# main.net
KiCad netlist of a schematic drawn in Altium Designer
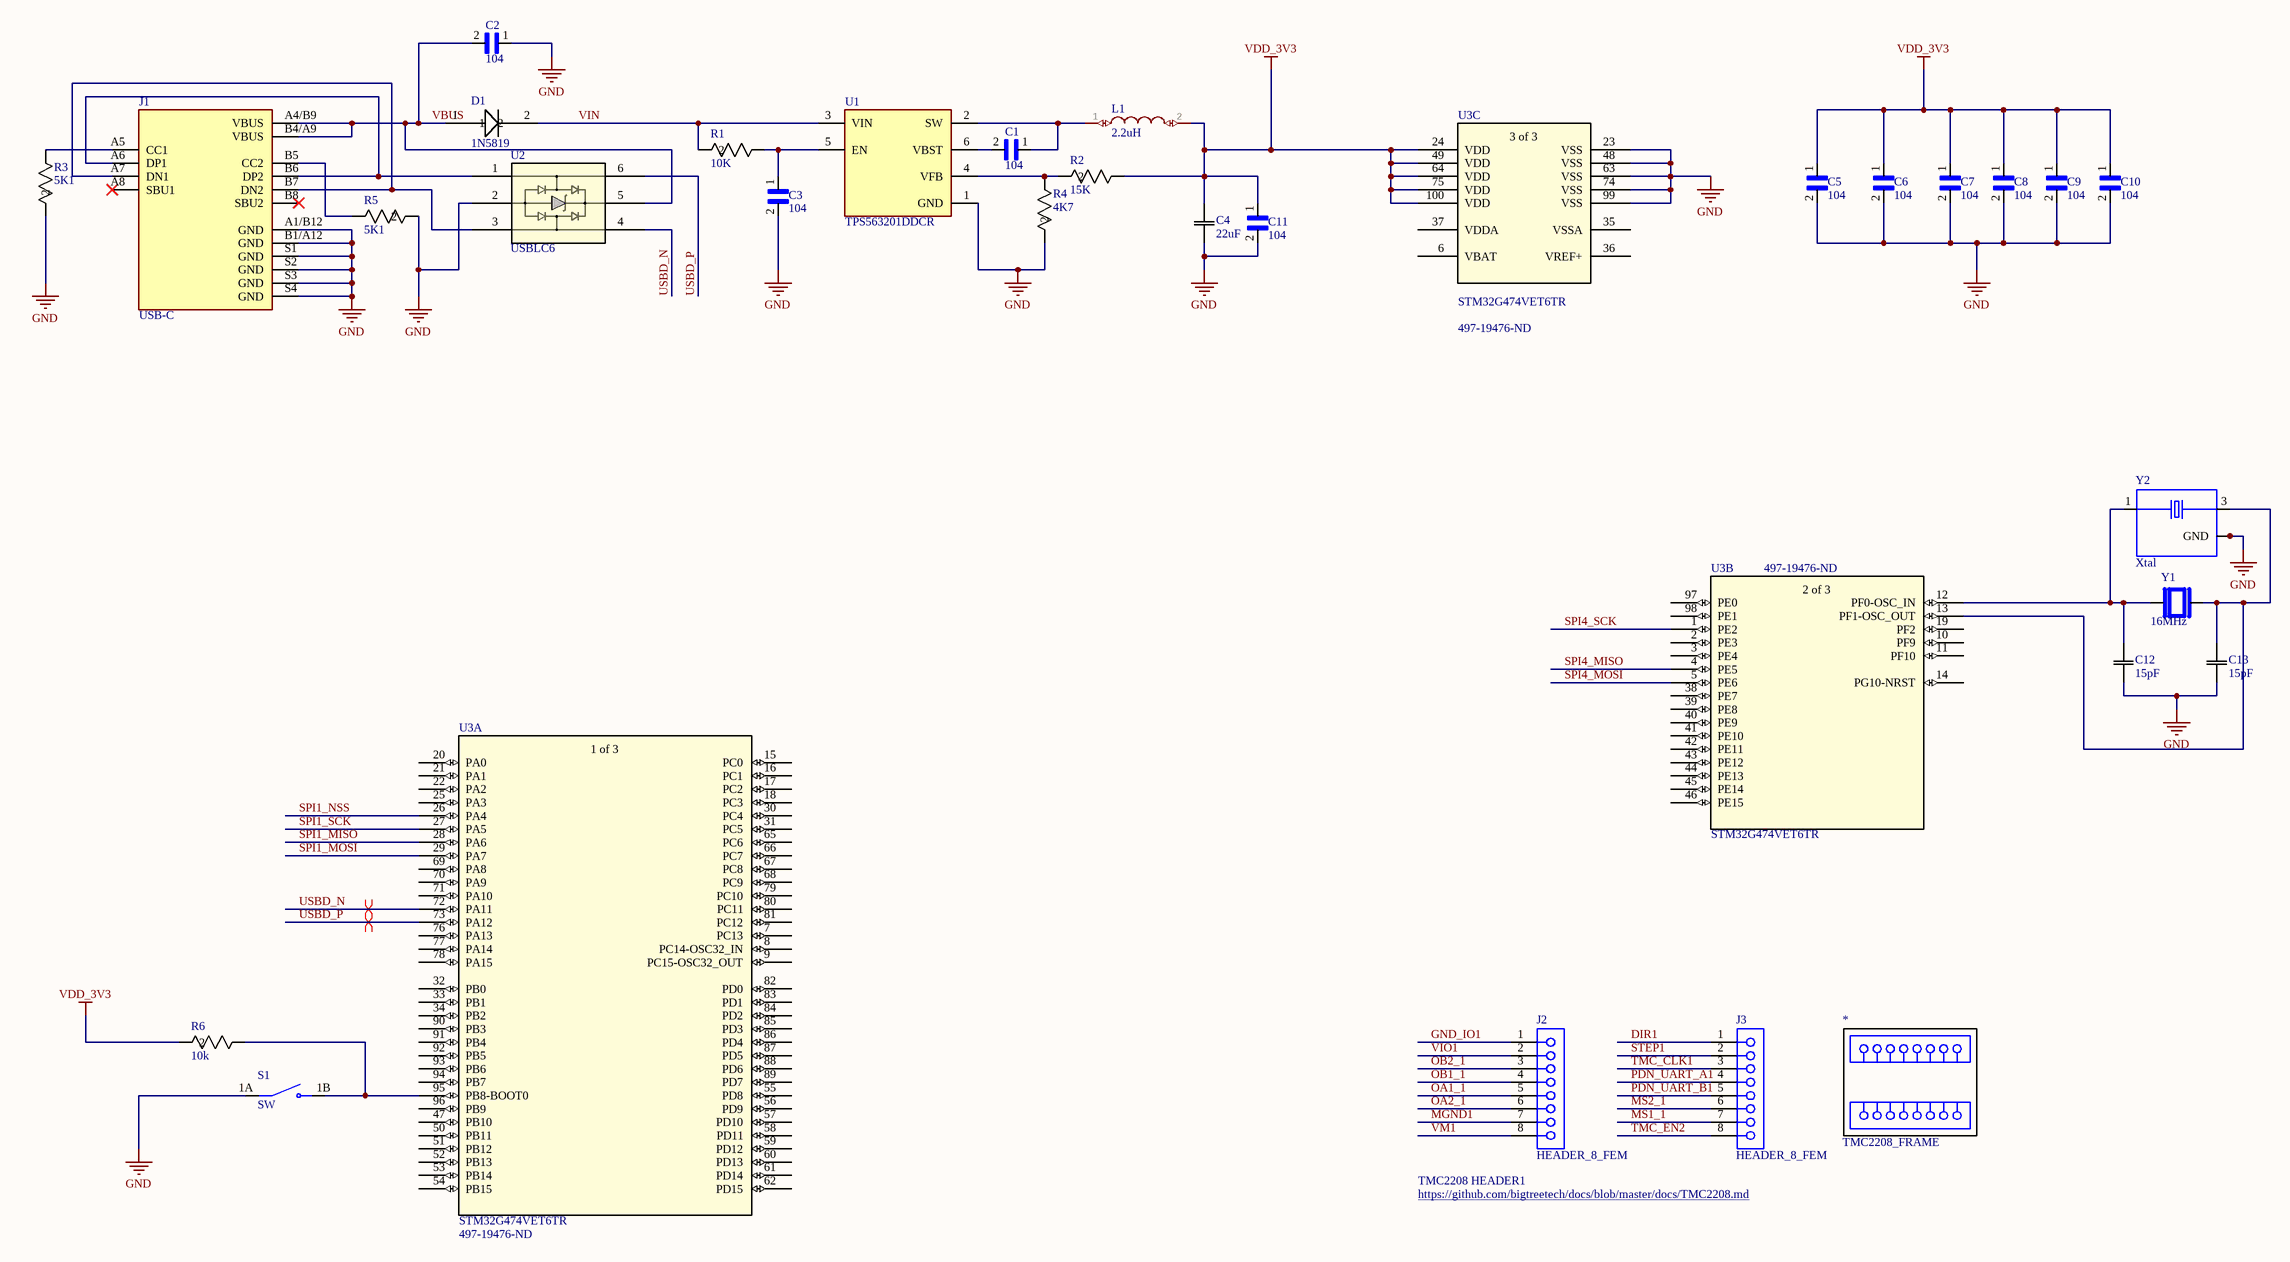
[diagram p0: main.SchDoc]

(export (version "E")
  (design (tool "Eeschema 10.0.6"))
  (components
    (comp (ref "*") (value "TMC2208_FRAME") (libsource (lib "Inproject") (part "TMC2208_FRAME")))
    (comp (ref "C1")
      (value "104")
      (footprint "CAPC1005X55N2")
      (description "Multilayer Ceramic Capacitor, 0.1 uF, 16 V, ï¿½ 10%, X7R, 0402 [1005 Metric]")
      (fields
        (field (name "MANUFACTURER") "Yageo")
        (field (name "MANUFACTURER PART NUMBER") "CC0402KRX7R7BB104")
      )
      (libsource (lib "") (part "CC0402KRX7R7BB104_1"))
    )
    (comp (ref "C2")
      (value "104")
      (footprint "CAPC1005X55N2")
      (description "Multilayer Ceramic Capacitor, 0.1 uF, 16 V, ï¿½ 10%, X7R, 0402 [1005 Metric]")
      (fields
        (field (name "MANUFACTURER") "Yageo")
        (field (name "MANUFACTURER PART NUMBER") "CC0402KRX7R7BB104")
      )
      (libsource (lib "") (part "CC0402KRX7R7BB104_1"))
    )
    (comp (ref "C3")
      (value "104")
      (footprint "CAPC1005X55N2")
      (description "Multilayer Ceramic Capacitor, 0.1 uF, 16 V, ï¿½ 10%, X7R, 0402 [1005 Metric]")
      (fields
        (field (name "MANUFACTURER") "Yageo")
        (field (name "MANUFACTURER PART NUMBER") "CC0402KRX7R7BB104")
      )
      (libsource (lib "Inproject") (part "CC0402KRX7R7BB104"))
    )
    (comp (ref "C4")
      (value "22uF")
      (footprint "CAP_CC0805_YAG")
      (description "Multilayer Ceramic Capacitor, 22 uF, 10 V, ± 20%, X5R, 0805 [2012 Metric]")
      (fields
        (field (name "MANUFACTURER") "Yageo")
        (field (name "MANUFACTURER PART NUMBER") "CC0805MKX5R6BB226")
      )
      (libsource (lib "Inproject") (part "CC0805MKX5R6BB226"))
    )
    (comp (ref "C5")
      (value "104")
      (footprint "CAPC1005X55N2")
      (description "Multilayer Ceramic Capacitor, 0.1 uF, 16 V, ï¿½ 10%, X7R, 0402 [1005 Metric]")
      (fields
        (field (name "MANUFACTURER") "Yageo")
        (field (name "MANUFACTURER PART NUMBER") "CC0402KRX7R7BB104")
      )
      (libsource (lib "Inproject") (part "CC0402KRX7R7BB104"))
    )
    (comp (ref "C6")
      (value "104")
      (footprint "CAPC1005X55N2")
      (description "Multilayer Ceramic Capacitor, 0.1 uF, 16 V, ï¿½ 10%, X7R, 0402 [1005 Metric]")
      (fields
        (field (name "MANUFACTURER") "Yageo")
        (field (name "MANUFACTURER PART NUMBER") "CC0402KRX7R7BB104")
      )
      (libsource (lib "Inproject") (part "CC0402KRX7R7BB104"))
    )
    (comp (ref "C7")
      (value "104")
      (footprint "CAPC1005X55N2")
      (description "Multilayer Ceramic Capacitor, 0.1 uF, 16 V, ï¿½ 10%, X7R, 0402 [1005 Metric]")
      (fields
        (field (name "MANUFACTURER") "Yageo")
        (field (name "MANUFACTURER PART NUMBER") "CC0402KRX7R7BB104")
      )
      (libsource (lib "Inproject") (part "CC0402KRX7R7BB104"))
    )
    (comp (ref "C8")
      (value "104")
      (footprint "CAPC1005X55N2")
      (description "Multilayer Ceramic Capacitor, 0.1 uF, 16 V, ï¿½ 10%, X7R, 0402 [1005 Metric]")
      (fields
        (field (name "MANUFACTURER") "Yageo")
        (field (name "MANUFACTURER PART NUMBER") "CC0402KRX7R7BB104")
      )
      (libsource (lib "Inproject") (part "CC0402KRX7R7BB104"))
    )
    (comp (ref "C9")
      (value "104")
      (footprint "CAPC1005X55N2")
      (description "Multilayer Ceramic Capacitor, 0.1 uF, 16 V, ï¿½ 10%, X7R, 0402 [1005 Metric]")
      (fields
        (field (name "MANUFACTURER") "Yageo")
        (field (name "MANUFACTURER PART NUMBER") "CC0402KRX7R7BB104")
      )
      (libsource (lib "Inproject") (part "CC0402KRX7R7BB104"))
    )
    (comp (ref "C10")
      (value "104")
      (footprint "CAPC1005X55N2")
      (description "Multilayer Ceramic Capacitor, 0.1 uF, 16 V, ï¿½ 10%, X7R, 0402 [1005 Metric]")
      (fields
        (field (name "MANUFACTURER") "Yageo")
        (field (name "MANUFACTURER PART NUMBER") "CC0402KRX7R7BB104")
      )
      (libsource (lib "Inproject") (part "CC0402KRX7R7BB104"))
    )
    (comp (ref "C11")
      (value "104")
      (footprint "CAPC1005X55N2")
      (description "Multilayer Ceramic Capacitor, 0.1 uF, 16 V, ï¿½ 10%, X7R, 0402 [1005 Metric]")
      (fields
        (field (name "MANUFACTURER") "Yageo")
        (field (name "MANUFACTURER PART NUMBER") "CC0402KRX7R7BB104")
      )
      (libsource (lib "Inproject") (part "CC0402KRX7R7BB104"))
    )
    (comp (ref "C12")
      (value "15pF")
      (footprint "CC0402N_YAG-L")
      (description "Multilayer Ceramic Capacitor, 15 pF, 50 V, ± 5%, C0G (NP0), 0402 [1005 Metric]")
      (fields
        (field (name "MANUFACTURER") "Yageo")
        (field (name "MANUFACTURER PART NUMBER") "CC0402JRNPO9BN150")
      )
      (libsource (lib "Inproject") (part "CC0402JRNPO9BN150"))
    )
    (comp (ref "C13")
      (value "15pF")
      (footprint "CC0402N_YAG-L")
      (description "Multilayer Ceramic Capacitor, 15 pF, 50 V, ± 5%, C0G (NP0), 0402 [1005 Metric]")
      (fields
        (field (name "MANUFACTURER") "Yageo")
        (field (name "MANUFACTURER PART NUMBER") "CC0402JRNPO9BN150")
      )
      (libsource (lib "Inproject") (part "CC0402JRNPO9BN150"))
    )
    (comp (ref "D1")
      (value "1N5819")
      (footprint "1N5819HW-7-F_DIO")
      (description "1N5819HW Series 40 V 1 A Surface Mount Schottky Barrier Rectifier - SOD-123")
      (fields (field (name "MANUFACTURER") "Diodes") (field (name "MANUFACTURER PART NUMBER") "1N5819HW-7-F"))
      (libsource (lib "Inproject") (part "1N5819HW-7-F"))
    )
    (comp (ref "J1")
      (value "USB-C")
      (footprint "GCT_USB4110GFA")
      (description "USB Connector, 16 Contact(s), Male, Right Angle, Surface Mount Terminal, Locking, Receptacle")
      (fields
        (field (name "MANUFACTURER") "Global Connector Technology")
        (field (name "MANUFACTURER PART NUMBER") "USB4110-GF-A")
      )
      (libsource (lib "Inproject") (part "USB4110-GF-A"))
    )
    (comp (ref "J2")
      (value "HEADER_8_FEM")
      (footprint "HEADER_8_FEM")
      (description "Btb Conn, Rcpt, 8Pos, 1Row, 2.54Mm Rohs Compliant: Yes ¦Wurth Elektronik 61300811821")
      (fields
        (field (name "MANUFACTURER") "Wurth Electronics")
        (field (name "MANUFACTURER PART NUMBER") "61300811821")
      )
      (libsource (lib "Inproject") (part "HEADER_8_FEM"))
    )
    (comp (ref "J3")
      (value "HEADER_8_FEM")
      (footprint "HEADER_8_FEM")
      (description "Btb Conn, Rcpt, 8Pos, 1Row, 2.54Mm Rohs Compliant: Yes ¦Wurth Elektronik 61300811821")
      (fields
        (field (name "MANUFACTURER") "Wurth Electronics")
        (field (name "MANUFACTURER PART NUMBER") "61300811821")
      )
      (libsource (lib "Inproject") (part "HEADER_8_FEM"))
    )
    (comp (ref "L1")
      (value "2.2uH")
      (footprint "CDRH2D14")
      (description "2.2µH Shielded  Inductor 1.6A 94 mOhm Max Nonstandard")
      (fields
        (field (name "MANUFACTURER") "Sumida")
        (field (name "MANUFACTURER PART NUMBER") "CDRH2D14NP-2R2NC")
      )
      (libsource (lib "Inproject") (part "CDRH2D14NP-2R2NC"))
    )
    (comp (ref "R1")
      (value "10K")
      (footprint "RC0402")
      (description "SMD Chip Resistor, 10 kOhm, ï¿½ 1%, 62.5 mW, 0402 [1005 Metric], Thick Film, General Purpose")
      (fields
        (field (name "MANUFACTURER") "Yageo")
        (field (name "MANUFACTURER PART NUMBER") "RC0402FR-0710KL")
      )
      (libsource (lib "Inproject") (part "RC0402FR-0710KL"))
    )
    (comp (ref "R2")
      (value "15K")
      (footprint "RC0402")
      (description "Res Thin Film 0402 15K Ohm 0.1% 0.063W(1/16W) ±25ppm/C Pad SMD T/R")
      (fields
        (field (name "MANUFACTURER") "Yageo")
        (field (name "MANUFACTURER PART NUMBER") "RT0402BRD0715KL")
      )
      (libsource (lib "Inproject") (part "RT0402BRD0715KL"))
    )
    (comp (ref "R3")
      (value "5K1")
      (footprint "RC0402")
      (description "SMD Chip Resistor, 5.1 kOhm, ï¿½ 1%, 62.5 mW, 0402 [1005 Metric], Thick Film, General Purpose")
      (fields
        (field (name "MANUFACTURER") "Yageo")
        (field (name "MANUFACTURER PART NUMBER") "RC0402FR-075K1L")
      )
      (libsource (lib "Inproject") (part "RC0402FR-075K1L"))
    )
    (comp (ref "R4")
      (value "4K7")
      (footprint "RC0402")
      (description "SMD Chip Resistor, 4.7 kOhm, ï¿½ 5%, 62.5 mW, 0402 [1005 Metric], Thick Film, General Purpose")
      (fields
        (field (name "MANUFACTURER") "Yageo")
        (field (name "MANUFACTURER PART NUMBER") "RC0402JR-074K7L")
      )
      (libsource (lib "Inproject") (part "RC0402JR-074K7L"))
    )
    (comp (ref "R5")
      (value "5K1")
      (footprint "RC0402")
      (description "SMD Chip Resistor, 5.1 kOhm, ï¿½ 1%, 62.5 mW, 0402 [1005 Metric], Thick Film, General Purpose")
      (fields
        (field (name "MANUFACTURER") "Yageo")
        (field (name "MANUFACTURER PART NUMBER") "RC0402FR-075K1L")
      )
      (libsource (lib "Inproject") (part "RC0402FR-075K1L"))
    )
    (comp (ref "R6")
      (value "10k")
      (footprint "RC0402")
      (description "SMD Chip Resistor, 10 kOhm, ï¿½ 1%, 62.5 mW, 0402 [1005 Metric], Thick Film, General Purpose")
      (fields
        (field (name "MANUFACTURER") "Yageo")
        (field (name "MANUFACTURER PART NUMBER") "RC0402FR-0710KL")
      )
      (libsource (lib "Inproject") (part "RC0402FR-0710KL"))
    )
    (comp (ref "S1")
      (value "SW")
      (footprint "SW_DS04-254-2-01BK-SMT")
      (description "Switch DIP OFF ON SPST 1 Flat Slide 0.025A 24VDC Gull Wing 2.54mm SMD Tube")
      (fields
        (field (name "MANUFACTURER") "CUI Devices")
        (field (name "MANUFACTURER PART NUMBER") "DS04-254-2-01BK-SMT")
      )
      (libsource (lib "Inproject") (part "DS04-254-2-01BK-SMT"))
    )
    (comp (ref "U1")
      (value "TPS563201DDCR")
      (footprint "SOT95P280X110-6N")
      (description "Conv DC-DC 4.5V to 17V Synchronous Step Down Single-Out 0.76V to 7V 3A 6-Pin TSOT-23 T/R")
      (fields (field (name "MANUFACTURER") "Texas Instruments"))
      (libsource (lib "Inproject") (part "TPS563201DDCR"))
    )
    (comp (ref "U2")
      (value "USBLC6")
      (footprint "SOT23-6L_STM")
      (description "ESD Suppressor Diode Array Dual Uni-Dir 15kV Air Gap/15kV Contact Disc 6-Pin SOT-23 T/R")
      (fields
        (field (name "MANUFACTURER") "STMicroelectronics")
        (field (name "MANUFACTURER PART NUMBER") "USBLC6-2SC6")
      )
      (libsource (lib "Inproject") (part "USBLC6-2SC6"))
    )
    (comp (ref "U3")
      (value "STM32G474VET6TR")
      (footprint "STM32G474VET6TR")
      (description "MCU 32-Bit ARM Cortex-M4F RISC 512KB Flash 1.71V to 3.6V 100-Pin LQFP Tray")
      (fields
        (field (name "MANUFACTURER") "STMicroelectronics")
        (field (name "MANUFACTURER PART NUMBER") "STM32G474VET6")
        (field (name "SUPPLIER PART NUMBER 1") "497-19476-ND")
      )
      (libsource (lib "Inproject") (part "STM32G474VET6"))
    )
    (comp (ref "Y1")
      (value "16MHz")
      (footprint "ABM3-16.000MHZ-D2Y-T")
      (description "Crystal 16MHz ±20ppm (Tol) ±30ppm (Stability) 18pF FUND 40Ohm 2-Pin Mini-CSMD T/R")
      (fields
        (field (name "MANUFACTURER") "Abracon")
        (field (name "MANUFACTURER PART NUMBER") "ABM3-16.000MHZ-D2Y-T")
      )
      (libsource (lib "Inproject") (part "ABM3-16.000MHZ-D2Y-T"))
    )
    (comp (ref "Y2")
      (value "Xtal")
      (footprint "OSCCC320X250X60N")
      (description "Crystal 16.0000MHZ 8PF SMD")
      (fields
        (field (name "MANUFACTURER") "Kyocera AVX")
        (field (name "MANUFACTURER PART NUMBER") "CX3225SB16000D0GZJC1")
      )
      (libsource (lib "Inproject") (part "CX3225SB16000D0GZJC1"))
    )
  )
  (nets
    (net (code "1") (name "/DIR1") (class "Default")
      (node (ref "J3") (pin "1") (pinfunction "1_1") (pintype "passive"))
    )
    (net (code "2") (name "/GND_IO1") (class "Default")
      (node (ref "J2") (pin "1") (pinfunction "1_1") (pintype "passive"))
    )
    (net (code "3") (name "/MGND1") (class "Default")
      (node (ref "J2") (pin "7") (pinfunction "7_7") (pintype "passive"))
    )
    (net (code "4") (name "/MS1_1") (class "Default")
      (node (ref "J3") (pin "7") (pinfunction "7_7") (pintype "passive"))
    )
    (net (code "5") (name "/MS2_1") (class "Default")
      (node (ref "J3") (pin "6") (pinfunction "6_6") (pintype "passive"))
    )
    (net (code "6") (name "/OA1_1") (class "Default")
      (node (ref "J2") (pin "5") (pinfunction "5_5") (pintype "passive"))
    )
    (net (code "7") (name "/OA2_1") (class "Default")
      (node (ref "J2") (pin "6") (pinfunction "6_6") (pintype "passive"))
    )
    (net (code "8") (name "/OB1_1") (class "Default")
      (node (ref "J2") (pin "4") (pinfunction "4_4") (pintype "passive"))
    )
    (net (code "9") (name "/OB2_1") (class "Default")
      (node (ref "J2") (pin "3") (pinfunction "3_3") (pintype "passive"))
    )
    (net (code "10") (name "/PDN_UART_A1") (class "Default")
      (node (ref "J3") (pin "4") (pinfunction "4_4") (pintype "passive"))
    )
    (net (code "11") (name "/PDN_UART_B1") (class "Default")
      (node (ref "J3") (pin "5") (pinfunction "5_5") (pintype "passive"))
    )
    (net (code "12") (name "/SPI1_MISO") (class "Default")
      (node (ref "U3") (pin "28") (pinfunction "PA6_28") (pintype "bidirectional"))
    )
    (net (code "13") (name "/SPI1_MOSI") (class "Default")
      (node (ref "U3") (pin "29") (pinfunction "PA7_29") (pintype "bidirectional"))
    )
    (net (code "14") (name "/SPI1_NSS") (class "Default")
      (node (ref "U3") (pin "26") (pinfunction "PA4_26") (pintype "bidirectional"))
    )
    (net (code "15") (name "/SPI1_SCK") (class "Default")
      (node (ref "U3") (pin "27") (pinfunction "PA5_27") (pintype "bidirectional"))
    )
    (net (code "16") (name "/SPI4_MISO") (class "Default")
      (node (ref "U3") (pin "4") (pinfunction "PE5_4") (pintype "bidirectional"))
    )
    (net (code "17") (name "/SPI4_MOSI") (class "Default")
      (node (ref "U3") (pin "5") (pinfunction "PE6_5") (pintype "bidirectional"))
    )
    (net (code "18") (name "/SPI4_SCK") (class "Default")
      (node (ref "U3") (pin "1") (pinfunction "PE2_1") (pintype "bidirectional"))
    )
    (net (code "19") (name "/STEP1") (class "Default")
      (node (ref "J3") (pin "2") (pinfunction "2_2") (pintype "passive"))
    )
    (net (code "20") (name "/TMC_CLK1") (class "Default")
      (node (ref "J3") (pin "3") (pinfunction "3_3") (pintype "passive"))
    )
    (net (code "21") (name "/TMC_EN2") (class "Default")
      (node (ref "J3") (pin "8") (pinfunction "8_8") (pintype "passive"))
    )
    (net (code "22") (name "/USBD_N") (class "Default")
      (node (ref "U2") (pin "4") (pinfunction "4_4") (pintype "passive"))
      (node (ref "U3") (pin "72") (pinfunction "PA11_72") (pintype "bidirectional"))
    )
    (net (code "23") (name "/USBD_P") (class "Default")
      (node (ref "U2") (pin "6") (pinfunction "6_6") (pintype "passive"))
      (node (ref "U3") (pin "73") (pinfunction "PA12_73") (pintype "bidirectional"))
    )
    (net (code "24") (name "/VBUS") (class "Default")
      (node (ref "C2") (pin "2") (pinfunction "2_2") (pintype "passive"))
      (node (ref "D1") (pin "1") (pinfunction "1_1") (pintype "passive"))
      (node (ref "J1") (pin "A4/B9") (pinfunction "VBUS_A4/B9") (pintype "passive"))
      (node (ref "J1") (pin "B4/A9") (pinfunction "VBUS_B4/A9") (pintype "passive"))
      (node (ref "U2") (pin "5") (pinfunction "5_5") (pintype "passive"))
    )
    (net (code "25") (name "/VIN") (class "Default")
      (node (ref "D1") (pin "2") (pinfunction "2_2") (pintype "passive"))
      (node (ref "R1") (pin "2") (pinfunction "2_2") (pintype "passive"))
      (node (ref "U1") (pin "3") (pinfunction "VIN_3") (pintype "passive"))
    )
    (net (code "26") (name "/VIO1") (class "Default")
      (node (ref "J2") (pin "2") (pinfunction "2_2") (pintype "passive"))
    )
    (net (code "27") (name "/VM1") (class "Default")
      (node (ref "J2") (pin "8") (pinfunction "8_8") (pintype "passive"))
    )
    (net (code "28") (name "GND") (class "Default")
      (node (ref "C10") (pin "2") (pinfunction "2_2") (pintype "passive"))
      (node (ref "C11") (pin "2") (pinfunction "2_2") (pintype "passive"))
      (node (ref "C12") (pin "1") (pinfunction "1_1") (pintype "passive"))
      (node (ref "C13") (pin "1") (pinfunction "1_1") (pintype "passive"))
      (node (ref "C2") (pin "1") (pinfunction "1_1") (pintype "passive"))
      (node (ref "C3") (pin "2") (pinfunction "2_2") (pintype "passive"))
      (node (ref "C4") (pin "1") (pinfunction "1_1") (pintype "passive"))
      (node (ref "C5") (pin "2") (pinfunction "2_2") (pintype "passive"))
      (node (ref "C6") (pin "2") (pinfunction "2_2") (pintype "passive"))
      (node (ref "C7") (pin "2") (pinfunction "2_2") (pintype "passive"))
      (node (ref "C8") (pin "2") (pinfunction "2_2") (pintype "passive"))
      (node (ref "C9") (pin "2") (pinfunction "2_2") (pintype "passive"))
      (node (ref "J1") (pin "A1/B12") (pinfunction "GND_A1/B12") (pintype "passive"))
      (node (ref "J1") (pin "B1/A12") (pinfunction "GND_B1/A12") (pintype "passive"))
      (node (ref "J1") (pin "S1") (pinfunction "GND_S1") (pintype "passive"))
      (node (ref "J1") (pin "S2") (pinfunction "GND_S2") (pintype "passive"))
      (node (ref "J1") (pin "S3") (pinfunction "GND_S3") (pintype "passive"))
      (node (ref "J1") (pin "S4") (pinfunction "GND_S4") (pintype "passive"))
      (node (ref "R3") (pin "2") (pinfunction "2_2") (pintype "passive"))
      (node (ref "R4") (pin "2") (pinfunction "2_2") (pintype "passive"))
      (node (ref "R5") (pin "2") (pinfunction "2_2") (pintype "passive"))
      (node (ref "S1") (pin "1A") (pinfunction "COM_1A") (pintype "passive"))
      (node (ref "U1") (pin "1") (pinfunction "GND_1") (pintype "passive"))
      (node (ref "U2") (pin "2") (pinfunction "2_2") (pintype "passive"))
      (node (ref "U3") (pin "23") (pinfunction "VSS_23") (pintype "power_in"))
      (node (ref "U3") (pin "48") (pinfunction "VSS_48") (pintype "power_in"))
      (node (ref "U3") (pin "63") (pinfunction "VSS_63") (pintype "power_in"))
      (node (ref "U3") (pin "74") (pinfunction "VSS_74") (pintype "power_in"))
      (node (ref "U3") (pin "99") (pinfunction "VSS_99") (pintype "power_in"))
      (node (ref "Y2") (pin "2") (pinfunction "GND_2") (pintype "power_in"))
      (node (ref "Y2") (pin "4") (pinfunction "GND_4") (pintype "power_in"))
    )
    (net (code "29") (name "Net-(J1-CC1)") (class "Default")
      (node (ref "J1") (pin "A5") (pinfunction "CC1_A5") (pintype "passive"))
      (node (ref "R3") (pin "1") (pinfunction "1_1") (pintype "passive"))
    )
    (net (code "30") (name "Net-(J1-CC2)") (class "Default")
      (node (ref "J1") (pin "B5") (pinfunction "CC2_B5") (pintype "passive"))
      (node (ref "R5") (pin "1") (pinfunction "1_1") (pintype "passive"))
    )
    (net (code "31") (name "Net-(J1-DN1)") (class "Default")
      (node (ref "J1") (pin "A7") (pinfunction "DN1_A7") (pintype "passive"))
      (node (ref "J1") (pin "B7") (pinfunction "DN2_B7") (pintype "passive"))
      (node (ref "U2") (pin "3") (pinfunction "3_3") (pintype "passive"))
    )
    (net (code "32") (name "Net-(J1-DP1)") (class "Default")
      (node (ref "J1") (pin "A6") (pinfunction "DP1_A6") (pintype "passive"))
      (node (ref "J1") (pin "B6") (pinfunction "DP2_B6") (pintype "passive"))
      (node (ref "U2") (pin "1") (pinfunction "1_1") (pintype "passive"))
    )
    (net (code "33") (name "Net-(S1-NO)") (class "Default")
      (node (ref "R6") (pin "1") (pinfunction "1_1") (pintype "passive"))
      (node (ref "S1") (pin "1B") (pinfunction "NO_1B") (pintype "passive"))
      (node (ref "U3") (pin "95") (pinfunction "PB8-BOOT0_95") (pintype "bidirectional"))
    )
    (net (code "34") (name "Net-(U1-EN)") (class "Default")
      (node (ref "C3") (pin "1") (pinfunction "1_1") (pintype "passive"))
      (node (ref "R1") (pin "1") (pinfunction "1_1") (pintype "passive"))
      (node (ref "U1") (pin "5") (pinfunction "EN_5") (pintype "passive"))
    )
    (net (code "35") (name "Net-(U1-SW)") (class "Default")
      (node (ref "C1") (pin "1") (pinfunction "1_1") (pintype "passive"))
      (node (ref "L1") (pin "1") (pinfunction "1_1") (pintype "bidirectional"))
      (node (ref "U1") (pin "2") (pinfunction "SW_2") (pintype "passive"))
    )
    (net (code "36") (name "Net-(U1-VBST)") (class "Default")
      (node (ref "C1") (pin "2") (pinfunction "2_2") (pintype "passive"))
      (node (ref "U1") (pin "6") (pinfunction "VBST_6") (pintype "passive"))
    )
    (net (code "37") (name "Net-(U1-VFB)") (class "Default")
      (node (ref "R2") (pin "2") (pinfunction "2_2") (pintype "passive"))
      (node (ref "R4") (pin "1") (pinfunction "1_1") (pintype "passive"))
      (node (ref "U1") (pin "4") (pinfunction "VFB_4") (pintype "passive"))
    )
    (net (code "38") (name "Net-(U3B-PF0-OSC_IN)") (class "Default")
      (node (ref "C12") (pin "2") (pinfunction "2_2") (pintype "passive"))
      (node (ref "U3") (pin "12") (pinfunction "PF0-OSC_IN_12") (pintype "bidirectional"))
      (node (ref "Y1") (pin "1") (pinfunction "1_1") (pintype "passive"))
      (node (ref "Y2") (pin "1") (pinfunction "1_1") (pintype "passive"))
    )
    (net (code "39") (name "Net-(U3B-PF1-OSC_OUT)") (class "Default")
      (node (ref "C13") (pin "2") (pinfunction "2_2") (pintype "passive"))
      (node (ref "U3") (pin "13") (pinfunction "PF1-OSC_OUT_13") (pintype "bidirectional"))
      (node (ref "Y1") (pin "2") (pinfunction "2_2") (pintype "passive"))
      (node (ref "Y2") (pin "3") (pinfunction "3_3") (pintype "passive"))
    )
    (net (code "40") (name "VDD_3V3") (class "Default")
      (node (ref "C10") (pin "1") (pinfunction "1_1") (pintype "passive"))
      (node (ref "C11") (pin "1") (pinfunction "1_1") (pintype "passive"))
      (node (ref "C4") (pin "2") (pinfunction "2_2") (pintype "passive"))
      (node (ref "C5") (pin "1") (pinfunction "1_1") (pintype "passive"))
      (node (ref "C6") (pin "1") (pinfunction "1_1") (pintype "passive"))
      (node (ref "C7") (pin "1") (pinfunction "1_1") (pintype "passive"))
      (node (ref "C8") (pin "1") (pinfunction "1_1") (pintype "passive"))
      (node (ref "C9") (pin "1") (pinfunction "1_1") (pintype "passive"))
      (node (ref "L1") (pin "2") (pinfunction "2_2") (pintype "bidirectional"))
      (node (ref "R2") (pin "1") (pinfunction "1_1") (pintype "passive"))
      (node (ref "R6") (pin "2") (pinfunction "2_2") (pintype "passive"))
      (node (ref "U3") (pin "100") (pinfunction "VDD_100") (pintype "power_in"))
      (node (ref "U3") (pin "24") (pinfunction "VDD_24") (pintype "power_in"))
      (node (ref "U3") (pin "49") (pinfunction "VDD_49") (pintype "power_in"))
      (node (ref "U3") (pin "64") (pinfunction "VDD_64") (pintype "power_in"))
      (node (ref "U3") (pin "75") (pinfunction "VDD_75") (pintype "power_in"))
    )
    (net (code "41") (name "unconnected-(J1-SBU1-PadA8)") (class "Default")
      (node (ref "J1") (pin "A8") (pinfunction "SBU1_A8") (pintype "passive+no_connect"))
    )
    (net (code "42") (name "unconnected-(J1-SBU2-PadB8)") (class "Default")
      (node (ref "J1") (pin "B8") (pinfunction "SBU2_B8") (pintype "passive+no_connect"))
    )
    (net (code "43") (name "unconnected-(U3A-PA0-Pad20)") (class "Default")
      (node (ref "U3") (pin "20") (pinfunction "PA0_20") (pintype "bidirectional"))
    )
    (net (code "44") (name "unconnected-(U3A-PA1-Pad21)") (class "Default")
      (node (ref "U3") (pin "21") (pinfunction "PA1_21") (pintype "bidirectional"))
    )
    (net (code "45") (name "unconnected-(U3A-PA2-Pad22)") (class "Default")
      (node (ref "U3") (pin "22") (pinfunction "PA2_22") (pintype "bidirectional"))
    )
    (net (code "46") (name "unconnected-(U3A-PA3-Pad25)") (class "Default")
      (node (ref "U3") (pin "25") (pinfunction "PA3_25") (pintype "bidirectional"))
    )
    (net (code "47") (name "unconnected-(U3A-PA8-Pad69)") (class "Default")
      (node (ref "U3") (pin "69") (pinfunction "PA8_69") (pintype "bidirectional"))
    )
    (net (code "48") (name "unconnected-(U3A-PA9-Pad70)") (class "Default")
      (node (ref "U3") (pin "70") (pinfunction "PA9_70") (pintype "bidirectional"))
    )
    (net (code "49") (name "unconnected-(U3A-PA10-Pad71)") (class "Default")
      (node (ref "U3") (pin "71") (pinfunction "PA10_71") (pintype "bidirectional"))
    )
    (net (code "50") (name "unconnected-(U3A-PA13-Pad76)") (class "Default")
      (node (ref "U3") (pin "76") (pinfunction "PA13_76") (pintype "bidirectional"))
    )
    (net (code "51") (name "unconnected-(U3A-PA14-Pad77)") (class "Default")
      (node (ref "U3") (pin "77") (pinfunction "PA14_77") (pintype "bidirectional"))
    )
    (net (code "52") (name "unconnected-(U3A-PA15-Pad78)") (class "Default")
      (node (ref "U3") (pin "78") (pinfunction "PA15_78") (pintype "bidirectional"))
    )
    (net (code "53") (name "unconnected-(U3A-PB0-Pad32)") (class "Default")
      (node (ref "U3") (pin "32") (pinfunction "PB0_32") (pintype "bidirectional"))
    )
    (net (code "54") (name "unconnected-(U3A-PB1-Pad33)") (class "Default")
      (node (ref "U3") (pin "33") (pinfunction "PB1_33") (pintype "bidirectional"))
    )
    (net (code "55") (name "unconnected-(U3A-PB2-Pad34)") (class "Default")
      (node (ref "U3") (pin "34") (pinfunction "PB2_34") (pintype "bidirectional"))
    )
    (net (code "56") (name "unconnected-(U3A-PB3-Pad90)") (class "Default")
      (node (ref "U3") (pin "90") (pinfunction "PB3_90") (pintype "bidirectional"))
    )
    (net (code "57") (name "unconnected-(U3A-PB4-Pad91)") (class "Default")
      (node (ref "U3") (pin "91") (pinfunction "PB4_91") (pintype "bidirectional"))
    )
    (net (code "58") (name "unconnected-(U3A-PB5-Pad92)") (class "Default")
      (node (ref "U3") (pin "92") (pinfunction "PB5_92") (pintype "bidirectional"))
    )
    (net (code "59") (name "unconnected-(U3A-PB6-Pad93)") (class "Default")
      (node (ref "U3") (pin "93") (pinfunction "PB6_93") (pintype "bidirectional"))
    )
    (net (code "60") (name "unconnected-(U3A-PB7-Pad94)") (class "Default")
      (node (ref "U3") (pin "94") (pinfunction "PB7_94") (pintype "bidirectional"))
    )
    (net (code "61") (name "unconnected-(U3A-PB9-Pad96)") (class "Default")
      (node (ref "U3") (pin "96") (pinfunction "PB9_96") (pintype "bidirectional"))
    )
    (net (code "62") (name "unconnected-(U3A-PB10-Pad47)") (class "Default")
      (node (ref "U3") (pin "47") (pinfunction "PB10_47") (pintype "bidirectional"))
    )
    (net (code "63") (name "unconnected-(U3A-PB11-Pad50)") (class "Default")
      (node (ref "U3") (pin "50") (pinfunction "PB11_50") (pintype "bidirectional"))
    )
    (net (code "64") (name "unconnected-(U3A-PB12-Pad51)") (class "Default")
      (node (ref "U3") (pin "51") (pinfunction "PB12_51") (pintype "bidirectional"))
    )
    (net (code "65") (name "unconnected-(U3A-PB13-Pad52)") (class "Default")
      (node (ref "U3") (pin "52") (pinfunction "PB13_52") (pintype "bidirectional"))
    )
    (net (code "66") (name "unconnected-(U3A-PB14-Pad53)") (class "Default")
      (node (ref "U3") (pin "53") (pinfunction "PB14_53") (pintype "bidirectional"))
    )
    (net (code "67") (name "unconnected-(U3A-PB15-Pad54)") (class "Default")
      (node (ref "U3") (pin "54") (pinfunction "PB15_54") (pintype "bidirectional"))
    )
    (net (code "68") (name "unconnected-(U3A-PC0-Pad15)") (class "Default")
      (node (ref "U3") (pin "15") (pinfunction "PC0_15") (pintype "bidirectional"))
    )
    (net (code "69") (name "unconnected-(U3A-PC1-Pad16)") (class "Default")
      (node (ref "U3") (pin "16") (pinfunction "PC1_16") (pintype "bidirectional"))
    )
    (net (code "70") (name "unconnected-(U3A-PC2-Pad17)") (class "Default")
      (node (ref "U3") (pin "17") (pinfunction "PC2_17") (pintype "bidirectional"))
    )
    (net (code "71") (name "unconnected-(U3A-PC3-Pad18)") (class "Default")
      (node (ref "U3") (pin "18") (pinfunction "PC3_18") (pintype "bidirectional"))
    )
    (net (code "72") (name "unconnected-(U3A-PC4-Pad30)") (class "Default")
      (node (ref "U3") (pin "30") (pinfunction "PC4_30") (pintype "bidirectional"))
    )
    (net (code "73") (name "unconnected-(U3A-PC5-Pad31)") (class "Default")
      (node (ref "U3") (pin "31") (pinfunction "PC5_31") (pintype "bidirectional"))
    )
    (net (code "74") (name "unconnected-(U3A-PC6-Pad65)") (class "Default")
      (node (ref "U3") (pin "65") (pinfunction "PC6_65") (pintype "bidirectional"))
    )
    (net (code "75") (name "unconnected-(U3A-PC7-Pad66)") (class "Default")
      (node (ref "U3") (pin "66") (pinfunction "PC7_66") (pintype "bidirectional"))
    )
    (net (code "76") (name "unconnected-(U3A-PC8-Pad67)") (class "Default")
      (node (ref "U3") (pin "67") (pinfunction "PC8_67") (pintype "bidirectional"))
    )
    (net (code "77") (name "unconnected-(U3A-PC9-Pad68)") (class "Default")
      (node (ref "U3") (pin "68") (pinfunction "PC9_68") (pintype "bidirectional"))
    )
    (net (code "78") (name "unconnected-(U3A-PC10-Pad79)") (class "Default")
      (node (ref "U3") (pin "79") (pinfunction "PC10_79") (pintype "bidirectional"))
    )
    (net (code "79") (name "unconnected-(U3A-PC11-Pad80)") (class "Default")
      (node (ref "U3") (pin "80") (pinfunction "PC11_80") (pintype "bidirectional"))
    )
    (net (code "80") (name "unconnected-(U3A-PC12-Pad81)") (class "Default")
      (node (ref "U3") (pin "81") (pinfunction "PC12_81") (pintype "bidirectional"))
    )
    (net (code "81") (name "unconnected-(U3A-PC13-Pad7)") (class "Default")
      (node (ref "U3") (pin "7") (pinfunction "PC13_7") (pintype "bidirectional"))
    )
    (net (code "82") (name "unconnected-(U3A-PC14-OSC32_IN-Pad8)") (class "Default")
      (node (ref "U3") (pin "8") (pinfunction "PC14-OSC32_IN_8") (pintype "bidirectional"))
    )
    (net (code "83") (name "unconnected-(U3A-PC15-OSC32_OUT-Pad9)") (class "Default")
      (node (ref "U3") (pin "9") (pinfunction "PC15-OSC32_OUT_9") (pintype "bidirectional"))
    )
    (net (code "84") (name "unconnected-(U3A-PD0-Pad82)") (class "Default")
      (node (ref "U3") (pin "82") (pinfunction "PD0_82") (pintype "bidirectional"))
    )
    (net (code "85") (name "unconnected-(U3A-PD1-Pad83)") (class "Default")
      (node (ref "U3") (pin "83") (pinfunction "PD1_83") (pintype "bidirectional"))
    )
    (net (code "86") (name "unconnected-(U3A-PD2-Pad84)") (class "Default")
      (node (ref "U3") (pin "84") (pinfunction "PD2_84") (pintype "bidirectional"))
    )
    (net (code "87") (name "unconnected-(U3A-PD3-Pad85)") (class "Default")
      (node (ref "U3") (pin "85") (pinfunction "PD3_85") (pintype "bidirectional"))
    )
    (net (code "88") (name "unconnected-(U3A-PD4-Pad86)") (class "Default")
      (node (ref "U3") (pin "86") (pinfunction "PD4_86") (pintype "bidirectional"))
    )
    (net (code "89") (name "unconnected-(U3A-PD5-Pad87)") (class "Default")
      (node (ref "U3") (pin "87") (pinfunction "PD5_87") (pintype "bidirectional"))
    )
    (net (code "90") (name "unconnected-(U3A-PD6-Pad88)") (class "Default")
      (node (ref "U3") (pin "88") (pinfunction "PD6_88") (pintype "bidirectional"))
    )
    (net (code "91") (name "unconnected-(U3A-PD7-Pad89)") (class "Default")
      (node (ref "U3") (pin "89") (pinfunction "PD7_89") (pintype "bidirectional"))
    )
    (net (code "92") (name "unconnected-(U3A-PD8-Pad55)") (class "Default")
      (node (ref "U3") (pin "55") (pinfunction "PD8_55") (pintype "bidirectional"))
    )
    (net (code "93") (name "unconnected-(U3A-PD9-Pad56)") (class "Default")
      (node (ref "U3") (pin "56") (pinfunction "PD9_56") (pintype "bidirectional"))
    )
    (net (code "94") (name "unconnected-(U3A-PD10-Pad57)") (class "Default")
      (node (ref "U3") (pin "57") (pinfunction "PD10_57") (pintype "bidirectional"))
    )
    (net (code "95") (name "unconnected-(U3A-PD11-Pad58)") (class "Default")
      (node (ref "U3") (pin "58") (pinfunction "PD11_58") (pintype "bidirectional"))
    )
    (net (code "96") (name "unconnected-(U3A-PD12-Pad59)") (class "Default")
      (node (ref "U3") (pin "59") (pinfunction "PD12_59") (pintype "bidirectional"))
    )
    (net (code "97") (name "unconnected-(U3A-PD13-Pad60)") (class "Default")
      (node (ref "U3") (pin "60") (pinfunction "PD13_60") (pintype "bidirectional"))
    )
    (net (code "98") (name "unconnected-(U3A-PD14-Pad61)") (class "Default")
      (node (ref "U3") (pin "61") (pinfunction "PD14_61") (pintype "bidirectional"))
    )
    (net (code "99") (name "unconnected-(U3A-PD15-Pad62)") (class "Default")
      (node (ref "U3") (pin "62") (pinfunction "PD15_62") (pintype "bidirectional"))
    )
    (net (code "100") (name "unconnected-(U3B-PE0-Pad97)") (class "Default")
      (node (ref "U3") (pin "97") (pinfunction "PE0_97") (pintype "bidirectional"))
    )
    (net (code "101") (name "unconnected-(U3B-PE1-Pad98)") (class "Default")
      (node (ref "U3") (pin "98") (pinfunction "PE1_98") (pintype "bidirectional"))
    )
    (net (code "102") (name "unconnected-(U3B-PE3-Pad2)") (class "Default")
      (node (ref "U3") (pin "2") (pinfunction "PE3_2") (pintype "bidirectional"))
    )
    (net (code "103") (name "unconnected-(U3B-PE4-Pad3)") (class "Default")
      (node (ref "U3") (pin "3") (pinfunction "PE4_3") (pintype "bidirectional"))
    )
    (net (code "104") (name "unconnected-(U3B-PE7-Pad38)") (class "Default")
      (node (ref "U3") (pin "38") (pinfunction "PE7_38") (pintype "bidirectional"))
    )
    (net (code "105") (name "unconnected-(U3B-PE8-Pad39)") (class "Default")
      (node (ref "U3") (pin "39") (pinfunction "PE8_39") (pintype "bidirectional"))
    )
    (net (code "106") (name "unconnected-(U3B-PE9-Pad40)") (class "Default")
      (node (ref "U3") (pin "40") (pinfunction "PE9_40") (pintype "bidirectional"))
    )
    (net (code "107") (name "unconnected-(U3B-PE10-Pad41)") (class "Default")
      (node (ref "U3") (pin "41") (pinfunction "PE10_41") (pintype "bidirectional"))
    )
    (net (code "108") (name "unconnected-(U3B-PE11-Pad42)") (class "Default")
      (node (ref "U3") (pin "42") (pinfunction "PE11_42") (pintype "bidirectional"))
    )
    (net (code "109") (name "unconnected-(U3B-PE12-Pad43)") (class "Default")
      (node (ref "U3") (pin "43") (pinfunction "PE12_43") (pintype "bidirectional"))
    )
    (net (code "110") (name "unconnected-(U3B-PE13-Pad44)") (class "Default")
      (node (ref "U3") (pin "44") (pinfunction "PE13_44") (pintype "bidirectional"))
    )
    (net (code "111") (name "unconnected-(U3B-PE14-Pad45)") (class "Default")
      (node (ref "U3") (pin "45") (pinfunction "PE14_45") (pintype "bidirectional"))
    )
    (net (code "112") (name "unconnected-(U3B-PE15-Pad46)") (class "Default")
      (node (ref "U3") (pin "46") (pinfunction "PE15_46") (pintype "bidirectional"))
    )
    (net (code "113") (name "unconnected-(U3B-PF2-Pad19)") (class "Default")
      (node (ref "U3") (pin "19") (pinfunction "PF2_19") (pintype "bidirectional"))
    )
    (net (code "114") (name "unconnected-(U3B-PF9-Pad10)") (class "Default")
      (node (ref "U3") (pin "10") (pinfunction "PF9_10") (pintype "bidirectional"))
    )
    (net (code "115") (name "unconnected-(U3B-PF10-Pad11)") (class "Default")
      (node (ref "U3") (pin "11") (pinfunction "PF10_11") (pintype "bidirectional"))
    )
    (net (code "116") (name "unconnected-(U3B-PG10-NRST-Pad14)") (class "Default")
      (node (ref "U3") (pin "14") (pinfunction "PG10-NRST_14") (pintype "bidirectional"))
    )
    (net (code "117") (name "unconnected-(U3C-VBAT-Pad6)") (class "Default")
      (node (ref "U3") (pin "6") (pinfunction "VBAT_6") (pintype "power_in"))
    )
    (net (code "118") (name "unconnected-(U3C-VDDA-Pad37)") (class "Default")
      (node (ref "U3") (pin "37") (pinfunction "VDDA_37") (pintype "power_in"))
    )
    (net (code "119") (name "unconnected-(U3C-VREF+-Pad36)") (class "Default")
      (node (ref "U3") (pin "36") (pinfunction "VREF+_36") (pintype "power_in"))
    )
    (net (code "120") (name "unconnected-(U3C-VSSA-Pad35)") (class "Default")
      (node (ref "U3") (pin "35") (pinfunction "VSSA_35") (pintype "power_in"))
    )
  )
)
